# 100068622_ideal_diode.net
KiCad netlist of a schematic drawn in Altium Designer
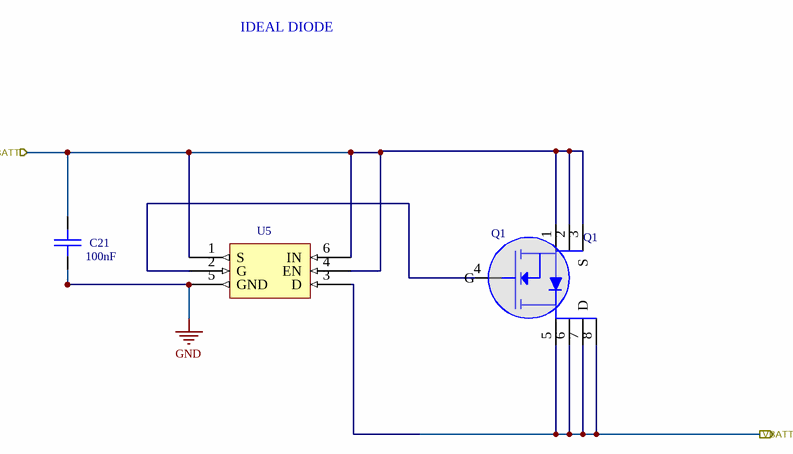
[diagram p0: 100068622_ideal_diode.SchDoc]

(export (version "E")
  (design (tool "Eeschema 10.0.6"))
  (components
    (comp (ref "C21")
      (value "100nF")
      (footprint "CAP-0402-A")
      (description "CAP 0402 0.1UF 50V 10% X5R")
      (fields (field (name "TOLERANCE") "10%"))
      (libsource (lib "Picatinny Server") (part "Capacitor - Non-Polarized"))
    )
    (comp (ref "Q1")
      (value "MOSFET - SINGLE - N CHANNEL - 8PIN")
      (footprint "IC-8PQFN-A")
      (description "Transistor MOSFET N-Channel 40V 150A 8-Pin PQFN T/R")
      (libsource (lib "Picatinny Server") (part "MOSFET - SINGLE - N CHANNEL - 8PIN"))
    )
    (comp (ref "U5")
      (value "NCV68261MTWAITBG")
      (footprint "IC-WDFN6-C")
      (description "OR Controller N-Channel Single 2.4Ohm Automotive 6-Pin WDFNW EP T/R")
      (libsource (lib "Picatinny Server") (part "NCV68261MTWAITBG"))
    )
  )
  (nets
    (net (code "1") (name "/VBATT") (class "Default")
      (node (ref "C21") (pin "2") (pinfunction "2_2") (pintype "passive"))
      (node (ref "Q1") (pin "1") (pinfunction "S_1") (pintype "passive"))
      (node (ref "Q1") (pin "2") (pinfunction "S_2") (pintype "passive"))
      (node (ref "Q1") (pin "3") (pinfunction "S_3") (pintype "passive"))
      (node (ref "U5") (pin "1") (pinfunction "S_1") (pintype "output"))
      (node (ref "U5") (pin "4") (pinfunction "EN_4") (pintype "input"))
      (node (ref "U5") (pin "6") (pinfunction "IN_6") (pintype "input"))
    )
    (net (code "2") (name "/VBATT_PROT") (class "Default")
      (node (ref "Q1") (pin "5") (pinfunction "D_5") (pintype "passive"))
      (node (ref "Q1") (pin "6") (pinfunction "D_6") (pintype "passive"))
      (node (ref "Q1") (pin "7") (pinfunction "D_7") (pintype "passive"))
      (node (ref "Q1") (pin "8") (pinfunction "D_8") (pintype "passive"))
      (node (ref "U5") (pin "3") (pinfunction "D_3") (pintype "input"))
    )
    (net (code "3") (name "GND") (class "Default")
      (node (ref "C21") (pin "1") (pinfunction "1_1") (pintype "passive"))
      (node (ref "U5") (pin "5") (pinfunction "GND_5") (pintype "output"))
    )
    (net (code "4") (name "Net-(Q1-G)") (class "Default")
      (node (ref "Q1") (pin "4") (pinfunction "G_4") (pintype "passive"))
      (node (ref "U5") (pin "2") (pinfunction "G_2") (pintype "input"))
    )
  )
)
